# converter.net
KiCad netlist of a schematic drawn in Altium Designer
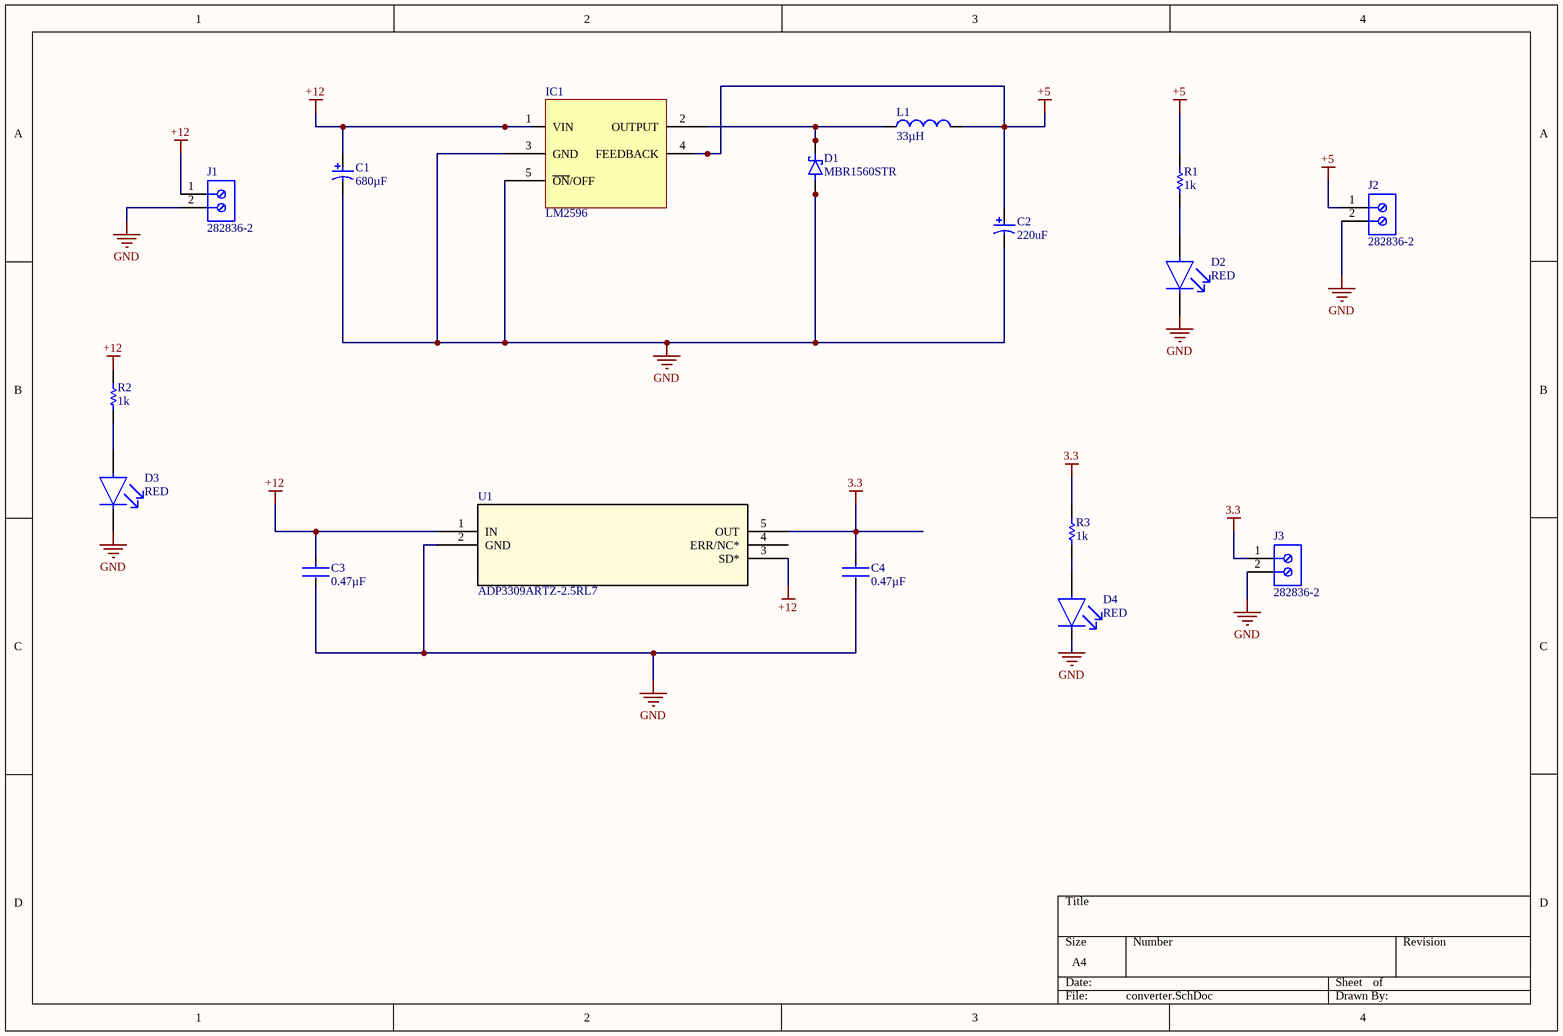
[diagram p0: converter.SchDoc]

(export (version "E")
  (design (tool "Eeschema 10.0.6"))
  (components
    (comp (ref "C1")
      (value "16SVP180M")
      (footprint "PNSC-SVP-E12_L")
      (fields (field (name "MANUFACTURER") "Panasonic") (field (name "CAPACITANCE") "680µF"))
      (libsource (lib "CASMarine Egitim LM2678") (part "CMP-2000-05492-1"))
    )
    (comp (ref "C2")
      (value "16SVP180M")
      (footprint "PNSC-SVP-E12_L")
      (fields (field (name "MANUFACTURER") "Panasonic") (field (name "CAPACITANCE") "220uF"))
      (libsource (lib "CASMarine Egitim LM2678") (part "CMP-2000-05492-1"))
    )
    (comp (ref "C3")
      (value "GRM188R71E474KA12D")
      (footprint "FP-GRM188-0_1-e0_2_0_5-MFG")
      (description "Chip Multilayer Ceramic Capacitors for General Purpose, 0603, 0.47uF, X7R, 15%, 10%, 25V")
      (fields
        (field (name "TOLERANCE") "10%")
        (field (name "VOLTAGE") "50V")
        (field (name "CAPACITANCE") "0.47µF")
      )
      (libsource (lib "CASMarine Egitim LM2678") (part "CMP-06035-003857-1"))
    )
    (comp (ref "C4")
      (value "GRM188R71E474KA12D")
      (footprint "FP-GRM188-0_1-e0_2_0_5-MFG")
      (description "Chip Multilayer Ceramic Capacitors for General Purpose, 0603, 0.47uF, X7R, 15%, 10%, 25V")
      (fields
        (field (name "TOLERANCE") "10%")
        (field (name "VOLTAGE") "50V")
        (field (name "CAPACITANCE") "0.47µF")
      )
      (libsource (lib "CASMarine Egitim LM2678") (part "CMP-06035-003857-1"))
    )
    (comp (ref "D1")
      (value "MBR1560STR")
      (footprint "DIO_MBR1560STR")
      (description "Diode Schottky 60V 15A Surface Mount TO-277B")
      (fields (field (name "MF") "SMC Diode Solutions"))
      (libsource (lib "CASMarine Egitim LM2678") (part "MBR1560STR"))
    )
    (comp (ref "D2")
      (value "150060RS75000")
      (footprint "FP-150060RS75000-MFG")
      (description "LED RED CLEAR 0603 SMD")
      (fields (field (name "MANUFACTURER") "Wurth Electronics") (field (name "COLOR") "RED"))
      (libsource (lib "CASMarine Egitim LM2678") (part "CMP-1426-00001-2"))
    )
    (comp (ref "D3")
      (value "150060RS75000")
      (footprint "FP-150060RS75000-MFG")
      (description "LED RED CLEAR 0603 SMD")
      (fields (field (name "MANUFACTURER") "Wurth Electronics") (field (name "COLOR") "RED"))
      (libsource (lib "CASMarine Egitim LM2678") (part "CMP-1426-00001-2"))
    )
    (comp (ref "D4")
      (value "150060RS75000")
      (footprint "FP-150060RS75000-MFG")
      (description "LED RED CLEAR 0603 SMD")
      (fields (field (name "MANUFACTURER") "Wurth Electronics") (field (name "COLOR") "RED"))
      (libsource (lib "CASMarine Egitim LM2678") (part "CMP-1426-00001-2"))
    )
    (comp (ref "IC1")
      (value "LM2596")
      (footprint "AltiumLive:D2PAK")
      (libsource (lib "AltiumLive") (part "LM2596"))
    )
    (comp (ref "J1")
      (value "282836-2")
      (footprint "TECO-282836-2_V")
      (description "Female Header, Pitch 5 mm, 1 x 2 Position, Height 10 mm, Tail Length 3.5 mm, Rohs, Bulk")
      (fields (field (name "VOLTAGE") "300V") (field (name "MANUFACTURER") "TE Connectivity"))
      (libsource (lib "CASMarine Egitim LM2678") (part "CMP-1684-00017-1"))
    )
    (comp (ref "J2")
      (value "282836-2")
      (footprint "TECO-282836-2_V")
      (description "Female Header, Pitch 5 mm, 1 x 2 Position, Height 10 mm, Tail Length 3.5 mm, Rohs, Bulk")
      (fields (field (name "VOLTAGE") "300V") (field (name "MANUFACTURER") "TE Connectivity"))
      (libsource (lib "CASMarine Egitim LM2678") (part "CMP-1684-00017-1"))
    )
    (comp (ref "J3")
      (value "282836-2")
      (footprint "TECO-282836-2_V")
      (description "Female Header, Pitch 5 mm, 1 x 2 Position, Height 10 mm, Tail Length 3.5 mm, Rohs, Bulk")
      (fields (field (name "VOLTAGE") "300V") (field (name "MANUFACTURER") "TE Connectivity"))
      (libsource (lib "CASMarine Egitim LM2678") (part "CMP-1684-00017-1"))
    )
    (comp (ref "L1")
      (value "7447709150")
      (footprint "WE-PD-XXL")
      (description "SMD-Shielded Power Inductor WE-PD, L = 15.0 µH")
      (fields (field (name "MANUFACTURER") "Wurth Electronics") (field (name "INDUCTANCE") "33µH"))
      (libsource (lib "CASMarine Egitim LM2678") (part "CMP-0227-00106-1"))
    )
    (comp (ref "R1")
      (value "ERJ-3EKF1001V")
      (footprint "RESC1608X55X30LL15T15")
      (fields
        (field (name "MANUFACTURER") "Panasonic")
        (field (name "MANUFACTURER PART NUMBER") "ERJ3EKF1001V")
        (field (name "TOLERANCE") "1%")
        (field (name "RESISTANCE") "1k")
      )
      (libsource (lib "CASMarine Egitim LM2678") (part "CMP-2000-00180-1"))
    )
    (comp (ref "R2")
      (value "ERJ-3EKF1001V")
      (footprint "RESC1608X55X30LL15T15")
      (fields
        (field (name "MANUFACTURER") "Panasonic")
        (field (name "MANUFACTURER PART NUMBER") "ERJ3EKF1001V")
        (field (name "TOLERANCE") "1%")
        (field (name "RESISTANCE") "1k")
      )
      (libsource (lib "CASMarine Egitim LM2678") (part "CMP-2000-00180-1"))
    )
    (comp (ref "R3")
      (value "ERJ-3EKF1001V")
      (footprint "RESC1608X55X30LL15T15")
      (fields
        (field (name "MANUFACTURER") "Panasonic")
        (field (name "MANUFACTURER PART NUMBER") "ERJ3EKF1001V")
        (field (name "TOLERANCE") "1%")
        (field (name "RESISTANCE") "1k")
      )
      (libsource (lib "CASMarine Egitim LM2678") (part "CMP-2000-00180-1"))
    )
    (comp (ref "U1")
      (value "ADP3309ARTZ-2.5RL7")
      (footprint "RJ_5_ADI")
      (description "No Description Available")
      (fields (field (name "COPYRIGHT") "Copyright (C) 2022 Ultra Librarian. All rights reserved."))
      (libsource (lib "ADP3309ARTZ-2P5RL7") (part "ADP3309ARTZ-2.5RL7"))
    )
  )
  (nets
    (net (code "1") (name "+5") (class "Default")
      (node (ref "C2") (pin "1") (pinfunction "1_1") (pintype "passive"))
      (node (ref "IC1") (pin "4") (pinfunction "FEEDBACK_4") (pintype "passive"))
      (node (ref "J2") (pin "1") (pinfunction "1_1") (pintype "passive"))
      (node (ref "L1") (pin "2") (pinfunction "2_2") (pintype "passive"))
      (node (ref "R1") (pin "1") (pinfunction "1_1") (pintype "passive"))
    )
    (net (code "2") (name "+12") (class "Default")
      (node (ref "C1") (pin "1") (pinfunction "1_1") (pintype "passive"))
      (node (ref "C3") (pin "1") (pinfunction "1_1") (pintype "passive"))
      (node (ref "IC1") (pin "1") (pinfunction "VIN_1") (pintype "passive"))
      (node (ref "J1") (pin "1") (pinfunction "1_1") (pintype "passive"))
      (node (ref "R2") (pin "2") (pinfunction "2_2") (pintype "passive"))
      (node (ref "U1") (pin "1") (pinfunction "IN_1") (pintype "passive"))
      (node (ref "U1") (pin "3") (pinfunction "SD*_3") (pintype "passive"))
    )
    (net (code "3") (name "3.3") (class "Default")
      (node (ref "C4") (pin "1") (pinfunction "1_1") (pintype "passive"))
      (node (ref "J3") (pin "1") (pinfunction "1_1") (pintype "passive"))
      (node (ref "R3") (pin "1") (pinfunction "1_1") (pintype "passive"))
      (node (ref "U1") (pin "5") (pinfunction "OUT_5") (pintype "passive"))
    )
    (net (code "4") (name "GND") (class "Default")
      (node (ref "C1") (pin "2") (pinfunction "2_2") (pintype "passive"))
      (node (ref "C2") (pin "2") (pinfunction "2_2") (pintype "passive"))
      (node (ref "C3") (pin "2") (pinfunction "2_2") (pintype "passive"))
      (node (ref "C4") (pin "2") (pinfunction "2_2") (pintype "passive"))
      (node (ref "D1") (pin "1") (pinfunction "A_1") (pintype "passive"))
      (node (ref "D1") (pin "2") (pinfunction "A_2") (pintype "passive"))
      (node (ref "D2") (pin "1") (pinfunction "C_1") (pintype "passive"))
      (node (ref "D3") (pin "1") (pinfunction "C_1") (pintype "passive"))
      (node (ref "D4") (pin "1") (pinfunction "C_1") (pintype "passive"))
      (node (ref "IC1") (pin "3") (pinfunction "GND_3") (pintype "passive"))
      (node (ref "IC1") (pin "5") (pinfunction "~{ON}/OFF_5") (pintype "passive"))
      (node (ref "J1") (pin "2") (pinfunction "2_2") (pintype "passive"))
      (node (ref "J2") (pin "2") (pinfunction "2_2") (pintype "passive"))
      (node (ref "J3") (pin "2") (pinfunction "2_2") (pintype "passive"))
      (node (ref "U1") (pin "2") (pinfunction "GND_2") (pintype "passive"))
    )
    (net (code "5") (name "Net-(D2-A)") (class "Default")
      (node (ref "D2") (pin "2") (pinfunction "A_2") (pintype "passive"))
      (node (ref "R1") (pin "2") (pinfunction "2_2") (pintype "passive"))
    )
    (net (code "6") (name "Net-(D3-A)") (class "Default")
      (node (ref "D3") (pin "2") (pinfunction "A_2") (pintype "passive"))
      (node (ref "R2") (pin "1") (pinfunction "1_1") (pintype "passive"))
    )
    (net (code "7") (name "Net-(D4-A)") (class "Default")
      (node (ref "D4") (pin "2") (pinfunction "A_2") (pintype "passive"))
      (node (ref "R3") (pin "2") (pinfunction "2_2") (pintype "passive"))
    )
    (net (code "8") (name "Net-(IC1-OUTPUT)") (class "Default")
      (node (ref "D1") (pin "3") (pinfunction "K_3") (pintype "passive"))
      (node (ref "D1") (pin "4") (pinfunction "K_4") (pintype "passive"))
      (node (ref "IC1") (pin "2") (pinfunction "OUTPUT_2") (pintype "passive"))
      (node (ref "L1") (pin "1") (pinfunction "1_1") (pintype "passive"))
    )
    (net (code "9") (name "unconnected-(U1-ERR{slash}NC*-Pad4)") (class "Default")
      (node (ref "U1") (pin "4") (pinfunction "ERR/NC*_4") (pintype "passive"))
    )
  )
)
